# pi-hat-v_02-sparkfun.net
KiCad netlist of a schematic drawn in EAGLE
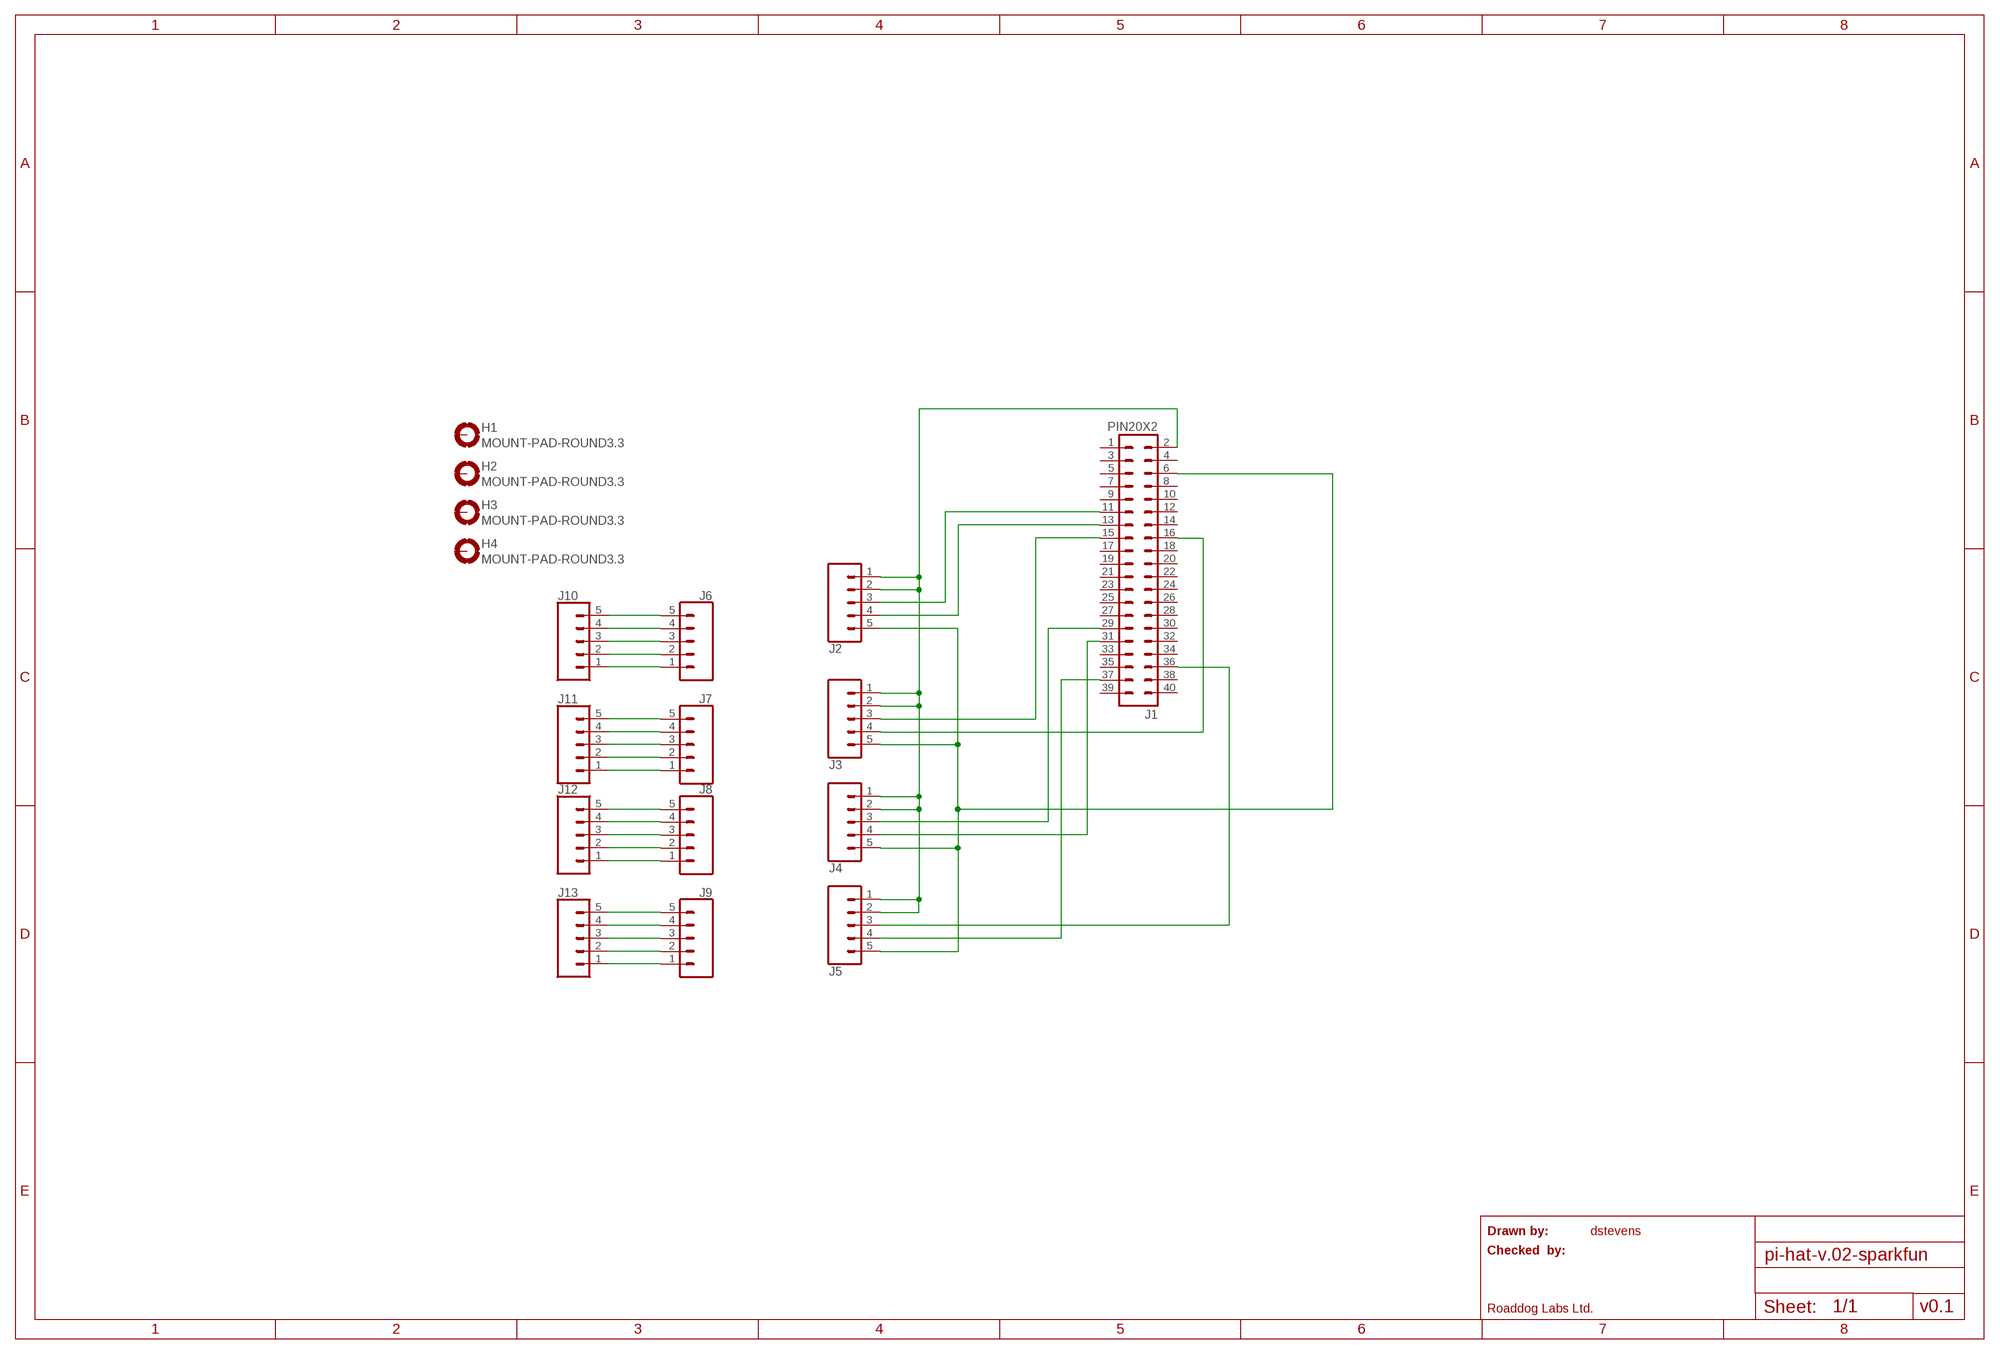
[diagram p0: schematic, sheet 1]

(export (version "E")
  (design (tool "Eeschema 10.0.6"))
  (components
    (comp (ref "H1")
      (value "MOUNT-PAD-ROUND3.3")
      (footprint "eagle-import:3,3-PAD")
      (libsource (lib "eagle-import") (part "MOUNT-PAD-ROUND3.3"))
    )
    (comp (ref "H2")
      (value "MOUNT-PAD-ROUND3.3")
      (footprint "eagle-import:3,3-PAD")
      (libsource (lib "eagle-import") (part "MOUNT-PAD-ROUND3.3"))
    )
    (comp (ref "H3")
      (value "MOUNT-PAD-ROUND3.3")
      (footprint "eagle-import:3,3-PAD")
      (libsource (lib "eagle-import") (part "MOUNT-PAD-ROUND3.3"))
    )
    (comp (ref "H4")
      (value "MOUNT-PAD-ROUND3.3")
      (footprint "eagle-import:3,3-PAD")
      (libsource (lib "eagle-import") (part "MOUNT-PAD-ROUND3.3"))
    )
    (comp (ref "J1")
      (value "PIN20X2")
      (footprint "eagle-import:PIN_20X2")
      (libsource (lib "eagle-import") (part "PIN20X2"))
    )
    (comp (ref "J2")
      (value "CONN_05")
      (footprint "eagle-import:1X05")
      (libsource (lib "eagle-import") (part "CONN_05"))
    )
    (comp (ref "J3")
      (value "CONN_05")
      (footprint "eagle-import:1X05")
      (libsource (lib "eagle-import") (part "CONN_05"))
    )
    (comp (ref "J4")
      (value "CONN_05")
      (footprint "eagle-import:1X05")
      (libsource (lib "eagle-import") (part "CONN_05"))
    )
    (comp (ref "J5")
      (value "CONN_05")
      (footprint "eagle-import:1X05")
      (libsource (lib "eagle-import") (part "CONN_05"))
    )
    (comp (ref "J6")
      (value "CONN_05")
      (footprint "eagle-import:1X05")
      (libsource (lib "eagle-import") (part "CONN_05"))
    )
    (comp (ref "J7")
      (value "CONN_05")
      (footprint "eagle-import:1X05")
      (libsource (lib "eagle-import") (part "CONN_05"))
    )
    (comp (ref "J8")
      (value "CONN_05")
      (footprint "eagle-import:1X05")
      (libsource (lib "eagle-import") (part "CONN_05"))
    )
    (comp (ref "J9")
      (value "CONN_05")
      (footprint "eagle-import:1X05")
      (libsource (lib "eagle-import") (part "CONN_05"))
    )
    (comp (ref "J10")
      (value "CONN_05")
      (footprint "eagle-import:1X05")
      (libsource (lib "eagle-import") (part "CONN_05"))
    )
    (comp (ref "J11")
      (value "CONN_05")
      (footprint "eagle-import:1X05")
      (libsource (lib "eagle-import") (part "CONN_05"))
    )
    (comp (ref "J12")
      (value "CONN_05")
      (footprint "eagle-import:1X05")
      (libsource (lib "eagle-import") (part "CONN_05"))
    )
    (comp (ref "J13")
      (value "CONN_05")
      (footprint "eagle-import:1X05")
      (libsource (lib "eagle-import") (part "CONN_05"))
    )
  )
  (nets
    (net (code "1") (name "Net-(J1-Pad2)") (class "Default")
      (node (ref "J1") (pin "2") (pinfunction "2_2") (pintype "passive"))
      (node (ref "J2") (pin "1") (pinfunction "1_1") (pintype "passive"))
      (node (ref "J2") (pin "2") (pinfunction "2_2") (pintype "passive"))
      (node (ref "J3") (pin "1") (pinfunction "1_1") (pintype "passive"))
      (node (ref "J3") (pin "2") (pinfunction "2_2") (pintype "passive"))
      (node (ref "J4") (pin "1") (pinfunction "1_1") (pintype "passive"))
      (node (ref "J4") (pin "2") (pinfunction "2_2") (pintype "passive"))
      (node (ref "J5") (pin "1") (pinfunction "1_1") (pintype "passive"))
      (node (ref "J5") (pin "2") (pinfunction "2_2") (pintype "passive"))
    )
    (net (code "2") (name "Net-(J1-Pad6)") (class "Default")
      (node (ref "J1") (pin "6") (pinfunction "6_6") (pintype "passive"))
      (node (ref "J2") (pin "5") (pinfunction "5_5") (pintype "passive"))
      (node (ref "J3") (pin "5") (pinfunction "5_5") (pintype "passive"))
      (node (ref "J4") (pin "5") (pinfunction "5_5") (pintype "passive"))
      (node (ref "J5") (pin "5") (pinfunction "5_5") (pintype "passive"))
    )
    (net (code "3") (name "Net-(J1-Pad11)") (class "Default")
      (node (ref "J1") (pin "11") (pinfunction "11_11") (pintype "passive"))
      (node (ref "J2") (pin "3") (pinfunction "3_3") (pintype "passive"))
    )
    (net (code "4") (name "Net-(J1-Pad13)") (class "Default")
      (node (ref "J1") (pin "13") (pinfunction "13_13") (pintype "passive"))
      (node (ref "J2") (pin "4") (pinfunction "4_4") (pintype "passive"))
    )
    (net (code "5") (name "Net-(J1-Pad15)") (class "Default")
      (node (ref "J1") (pin "15") (pinfunction "15_15") (pintype "passive"))
      (node (ref "J3") (pin "3") (pinfunction "3_3") (pintype "passive"))
    )
    (net (code "6") (name "Net-(J1-Pad16)") (class "Default")
      (node (ref "J1") (pin "16") (pinfunction "16_16") (pintype "passive"))
      (node (ref "J3") (pin "4") (pinfunction "4_4") (pintype "passive"))
    )
    (net (code "7") (name "Net-(J1-Pad29)") (class "Default")
      (node (ref "J1") (pin "29") (pinfunction "29_29") (pintype "passive"))
      (node (ref "J4") (pin "3") (pinfunction "3_3") (pintype "passive"))
    )
    (net (code "8") (name "Net-(J1-Pad31)") (class "Default")
      (node (ref "J1") (pin "31") (pinfunction "31_31") (pintype "passive"))
      (node (ref "J4") (pin "4") (pinfunction "4_4") (pintype "passive"))
    )
    (net (code "9") (name "Net-(J1-Pad36)") (class "Default")
      (node (ref "J1") (pin "36") (pinfunction "36_36") (pintype "passive"))
      (node (ref "J5") (pin "3") (pinfunction "3_3") (pintype "passive"))
    )
    (net (code "10") (name "Net-(J1-Pad37)") (class "Default")
      (node (ref "J1") (pin "37") (pinfunction "37_37") (pintype "passive"))
      (node (ref "J5") (pin "4") (pinfunction "4_4") (pintype "passive"))
    )
    (net (code "11") (name "Net-(J10-Pad1)") (class "Default")
      (node (ref "J10") (pin "1") (pinfunction "1_1") (pintype "passive"))
      (node (ref "J6") (pin "1") (pinfunction "1_1") (pintype "passive"))
    )
    (net (code "12") (name "Net-(J10-Pad2)") (class "Default")
      (node (ref "J10") (pin "2") (pinfunction "2_2") (pintype "passive"))
      (node (ref "J6") (pin "2") (pinfunction "2_2") (pintype "passive"))
    )
    (net (code "13") (name "Net-(J10-Pad3)") (class "Default")
      (node (ref "J10") (pin "3") (pinfunction "3_3") (pintype "passive"))
      (node (ref "J6") (pin "3") (pinfunction "3_3") (pintype "passive"))
    )
    (net (code "14") (name "Net-(J10-Pad4)") (class "Default")
      (node (ref "J10") (pin "4") (pinfunction "4_4") (pintype "passive"))
      (node (ref "J6") (pin "4") (pinfunction "4_4") (pintype "passive"))
    )
    (net (code "15") (name "Net-(J10-Pad5)") (class "Default")
      (node (ref "J10") (pin "5") (pinfunction "5_5") (pintype "passive"))
      (node (ref "J6") (pin "5") (pinfunction "5_5") (pintype "passive"))
    )
    (net (code "16") (name "Net-(J11-Pad1)") (class "Default")
      (node (ref "J11") (pin "1") (pinfunction "1_1") (pintype "passive"))
      (node (ref "J7") (pin "1") (pinfunction "1_1") (pintype "passive"))
    )
    (net (code "17") (name "Net-(J11-Pad2)") (class "Default")
      (node (ref "J11") (pin "2") (pinfunction "2_2") (pintype "passive"))
      (node (ref "J7") (pin "2") (pinfunction "2_2") (pintype "passive"))
    )
    (net (code "18") (name "Net-(J11-Pad3)") (class "Default")
      (node (ref "J11") (pin "3") (pinfunction "3_3") (pintype "passive"))
      (node (ref "J7") (pin "3") (pinfunction "3_3") (pintype "passive"))
    )
    (net (code "19") (name "Net-(J11-Pad4)") (class "Default")
      (node (ref "J11") (pin "4") (pinfunction "4_4") (pintype "passive"))
      (node (ref "J7") (pin "4") (pinfunction "4_4") (pintype "passive"))
    )
    (net (code "20") (name "Net-(J11-Pad5)") (class "Default")
      (node (ref "J11") (pin "5") (pinfunction "5_5") (pintype "passive"))
      (node (ref "J7") (pin "5") (pinfunction "5_5") (pintype "passive"))
    )
    (net (code "21") (name "Net-(J12-Pad1)") (class "Default")
      (node (ref "J12") (pin "1") (pinfunction "1_1") (pintype "passive"))
      (node (ref "J8") (pin "1") (pinfunction "1_1") (pintype "passive"))
    )
    (net (code "22") (name "Net-(J12-Pad2)") (class "Default")
      (node (ref "J12") (pin "2") (pinfunction "2_2") (pintype "passive"))
      (node (ref "J8") (pin "2") (pinfunction "2_2") (pintype "passive"))
    )
    (net (code "23") (name "Net-(J12-Pad3)") (class "Default")
      (node (ref "J12") (pin "3") (pinfunction "3_3") (pintype "passive"))
      (node (ref "J8") (pin "3") (pinfunction "3_3") (pintype "passive"))
    )
    (net (code "24") (name "Net-(J12-Pad4)") (class "Default")
      (node (ref "J12") (pin "4") (pinfunction "4_4") (pintype "passive"))
      (node (ref "J8") (pin "4") (pinfunction "4_4") (pintype "passive"))
    )
    (net (code "25") (name "Net-(J12-Pad5)") (class "Default")
      (node (ref "J12") (pin "5") (pinfunction "5_5") (pintype "passive"))
      (node (ref "J8") (pin "5") (pinfunction "5_5") (pintype "passive"))
    )
    (net (code "26") (name "Net-(J13-Pad1)") (class "Default")
      (node (ref "J13") (pin "1") (pinfunction "1_1") (pintype "passive"))
      (node (ref "J9") (pin "1") (pinfunction "1_1") (pintype "passive"))
    )
    (net (code "27") (name "Net-(J13-Pad2)") (class "Default")
      (node (ref "J13") (pin "2") (pinfunction "2_2") (pintype "passive"))
      (node (ref "J9") (pin "2") (pinfunction "2_2") (pintype "passive"))
    )
    (net (code "28") (name "Net-(J13-Pad3)") (class "Default")
      (node (ref "J13") (pin "3") (pinfunction "3_3") (pintype "passive"))
      (node (ref "J9") (pin "3") (pinfunction "3_3") (pintype "passive"))
    )
    (net (code "29") (name "Net-(J13-Pad4)") (class "Default")
      (node (ref "J13") (pin "4") (pinfunction "4_4") (pintype "passive"))
      (node (ref "J9") (pin "4") (pinfunction "4_4") (pintype "passive"))
    )
    (net (code "30") (name "Net-(J13-Pad5)") (class "Default")
      (node (ref "J13") (pin "5") (pinfunction "5_5") (pintype "passive"))
      (node (ref "J9") (pin "5") (pinfunction "5_5") (pintype "passive"))
    )
    (net (code "31") (name "unconnected-(H1-MOUNT-PadB3,3)") (class "Default")
      (node (ref "H1") (pin "B3,3") (pinfunction "MOUNT_B3,3") (pintype "passive"))
    )
    (net (code "32") (name "unconnected-(H2-MOUNT-PadB3,3)") (class "Default")
      (node (ref "H2") (pin "B3,3") (pinfunction "MOUNT_B3,3") (pintype "passive"))
    )
    (net (code "33") (name "unconnected-(H3-MOUNT-PadB3,3)") (class "Default")
      (node (ref "H3") (pin "B3,3") (pinfunction "MOUNT_B3,3") (pintype "passive"))
    )
    (net (code "34") (name "unconnected-(H4-MOUNT-PadB3,3)") (class "Default")
      (node (ref "H4") (pin "B3,3") (pinfunction "MOUNT_B3,3") (pintype "passive"))
    )
    (net (code "35") (name "unconnected-(J1-Pad1)") (class "Default")
      (node (ref "J1") (pin "1") (pinfunction "1_1") (pintype "passive"))
    )
    (net (code "36") (name "unconnected-(J1-Pad3)") (class "Default")
      (node (ref "J1") (pin "3") (pinfunction "3_3") (pintype "passive"))
    )
    (net (code "37") (name "unconnected-(J1-Pad4)") (class "Default")
      (node (ref "J1") (pin "4") (pinfunction "4_4") (pintype "passive"))
    )
    (net (code "38") (name "unconnected-(J1-Pad5)") (class "Default")
      (node (ref "J1") (pin "5") (pinfunction "5_5") (pintype "passive"))
    )
    (net (code "39") (name "unconnected-(J1-Pad7)") (class "Default")
      (node (ref "J1") (pin "7") (pinfunction "7_7") (pintype "passive"))
    )
    (net (code "40") (name "unconnected-(J1-Pad8)") (class "Default")
      (node (ref "J1") (pin "8") (pinfunction "8_8") (pintype "passive"))
    )
    (net (code "41") (name "unconnected-(J1-Pad9)") (class "Default")
      (node (ref "J1") (pin "9") (pinfunction "9_9") (pintype "passive"))
    )
    (net (code "42") (name "unconnected-(J1-Pad10)") (class "Default")
      (node (ref "J1") (pin "10") (pinfunction "10_10") (pintype "passive"))
    )
    (net (code "43") (name "unconnected-(J1-Pad12)") (class "Default")
      (node (ref "J1") (pin "12") (pinfunction "12_12") (pintype "passive"))
    )
    (net (code "44") (name "unconnected-(J1-Pad14)") (class "Default")
      (node (ref "J1") (pin "14") (pinfunction "14_14") (pintype "passive"))
    )
    (net (code "45") (name "unconnected-(J1-Pad17)") (class "Default")
      (node (ref "J1") (pin "17") (pinfunction "17_17") (pintype "passive"))
    )
    (net (code "46") (name "unconnected-(J1-Pad18)") (class "Default")
      (node (ref "J1") (pin "18") (pinfunction "18_18") (pintype "passive"))
    )
    (net (code "47") (name "unconnected-(J1-Pad19)") (class "Default")
      (node (ref "J1") (pin "19") (pinfunction "19_19") (pintype "passive"))
    )
    (net (code "48") (name "unconnected-(J1-Pad20)") (class "Default")
      (node (ref "J1") (pin "20") (pinfunction "20_20") (pintype "passive"))
    )
    (net (code "49") (name "unconnected-(J1-Pad21)") (class "Default")
      (node (ref "J1") (pin "21") (pinfunction "21_21") (pintype "passive"))
    )
    (net (code "50") (name "unconnected-(J1-Pad22)") (class "Default")
      (node (ref "J1") (pin "22") (pinfunction "22_22") (pintype "passive"))
    )
    (net (code "51") (name "unconnected-(J1-Pad23)") (class "Default")
      (node (ref "J1") (pin "23") (pinfunction "23_23") (pintype "passive"))
    )
    (net (code "52") (name "unconnected-(J1-Pad24)") (class "Default")
      (node (ref "J1") (pin "24") (pinfunction "24_24") (pintype "passive"))
    )
    (net (code "53") (name "unconnected-(J1-Pad25)") (class "Default")
      (node (ref "J1") (pin "25") (pinfunction "25_25") (pintype "passive"))
    )
    (net (code "54") (name "unconnected-(J1-Pad26)") (class "Default")
      (node (ref "J1") (pin "26") (pinfunction "26_26") (pintype "passive"))
    )
    (net (code "55") (name "unconnected-(J1-Pad27)") (class "Default")
      (node (ref "J1") (pin "27") (pinfunction "27_27") (pintype "passive"))
    )
    (net (code "56") (name "unconnected-(J1-Pad28)") (class "Default")
      (node (ref "J1") (pin "28") (pinfunction "28_28") (pintype "passive"))
    )
    (net (code "57") (name "unconnected-(J1-Pad30)") (class "Default")
      (node (ref "J1") (pin "30") (pinfunction "30_30") (pintype "passive"))
    )
    (net (code "58") (name "unconnected-(J1-Pad32)") (class "Default")
      (node (ref "J1") (pin "32") (pinfunction "32_32") (pintype "passive"))
    )
    (net (code "59") (name "unconnected-(J1-Pad33)") (class "Default")
      (node (ref "J1") (pin "33") (pinfunction "33_33") (pintype "passive"))
    )
    (net (code "60") (name "unconnected-(J1-Pad34)") (class "Default")
      (node (ref "J1") (pin "34") (pinfunction "34_34") (pintype "passive"))
    )
    (net (code "61") (name "unconnected-(J1-Pad35)") (class "Default")
      (node (ref "J1") (pin "35") (pinfunction "35_35") (pintype "passive"))
    )
    (net (code "62") (name "unconnected-(J1-Pad38)") (class "Default")
      (node (ref "J1") (pin "38") (pinfunction "38_38") (pintype "passive"))
    )
    (net (code "63") (name "unconnected-(J1-Pad39)") (class "Default")
      (node (ref "J1") (pin "39") (pinfunction "39_39") (pintype "passive"))
    )
    (net (code "64") (name "unconnected-(J1-Pad40)") (class "Default")
      (node (ref "J1") (pin "40") (pinfunction "40_40") (pintype "passive"))
    )
  )
)
